# CallerID_V11.net
KiCad netlist of a schematic drawn in EAGLE
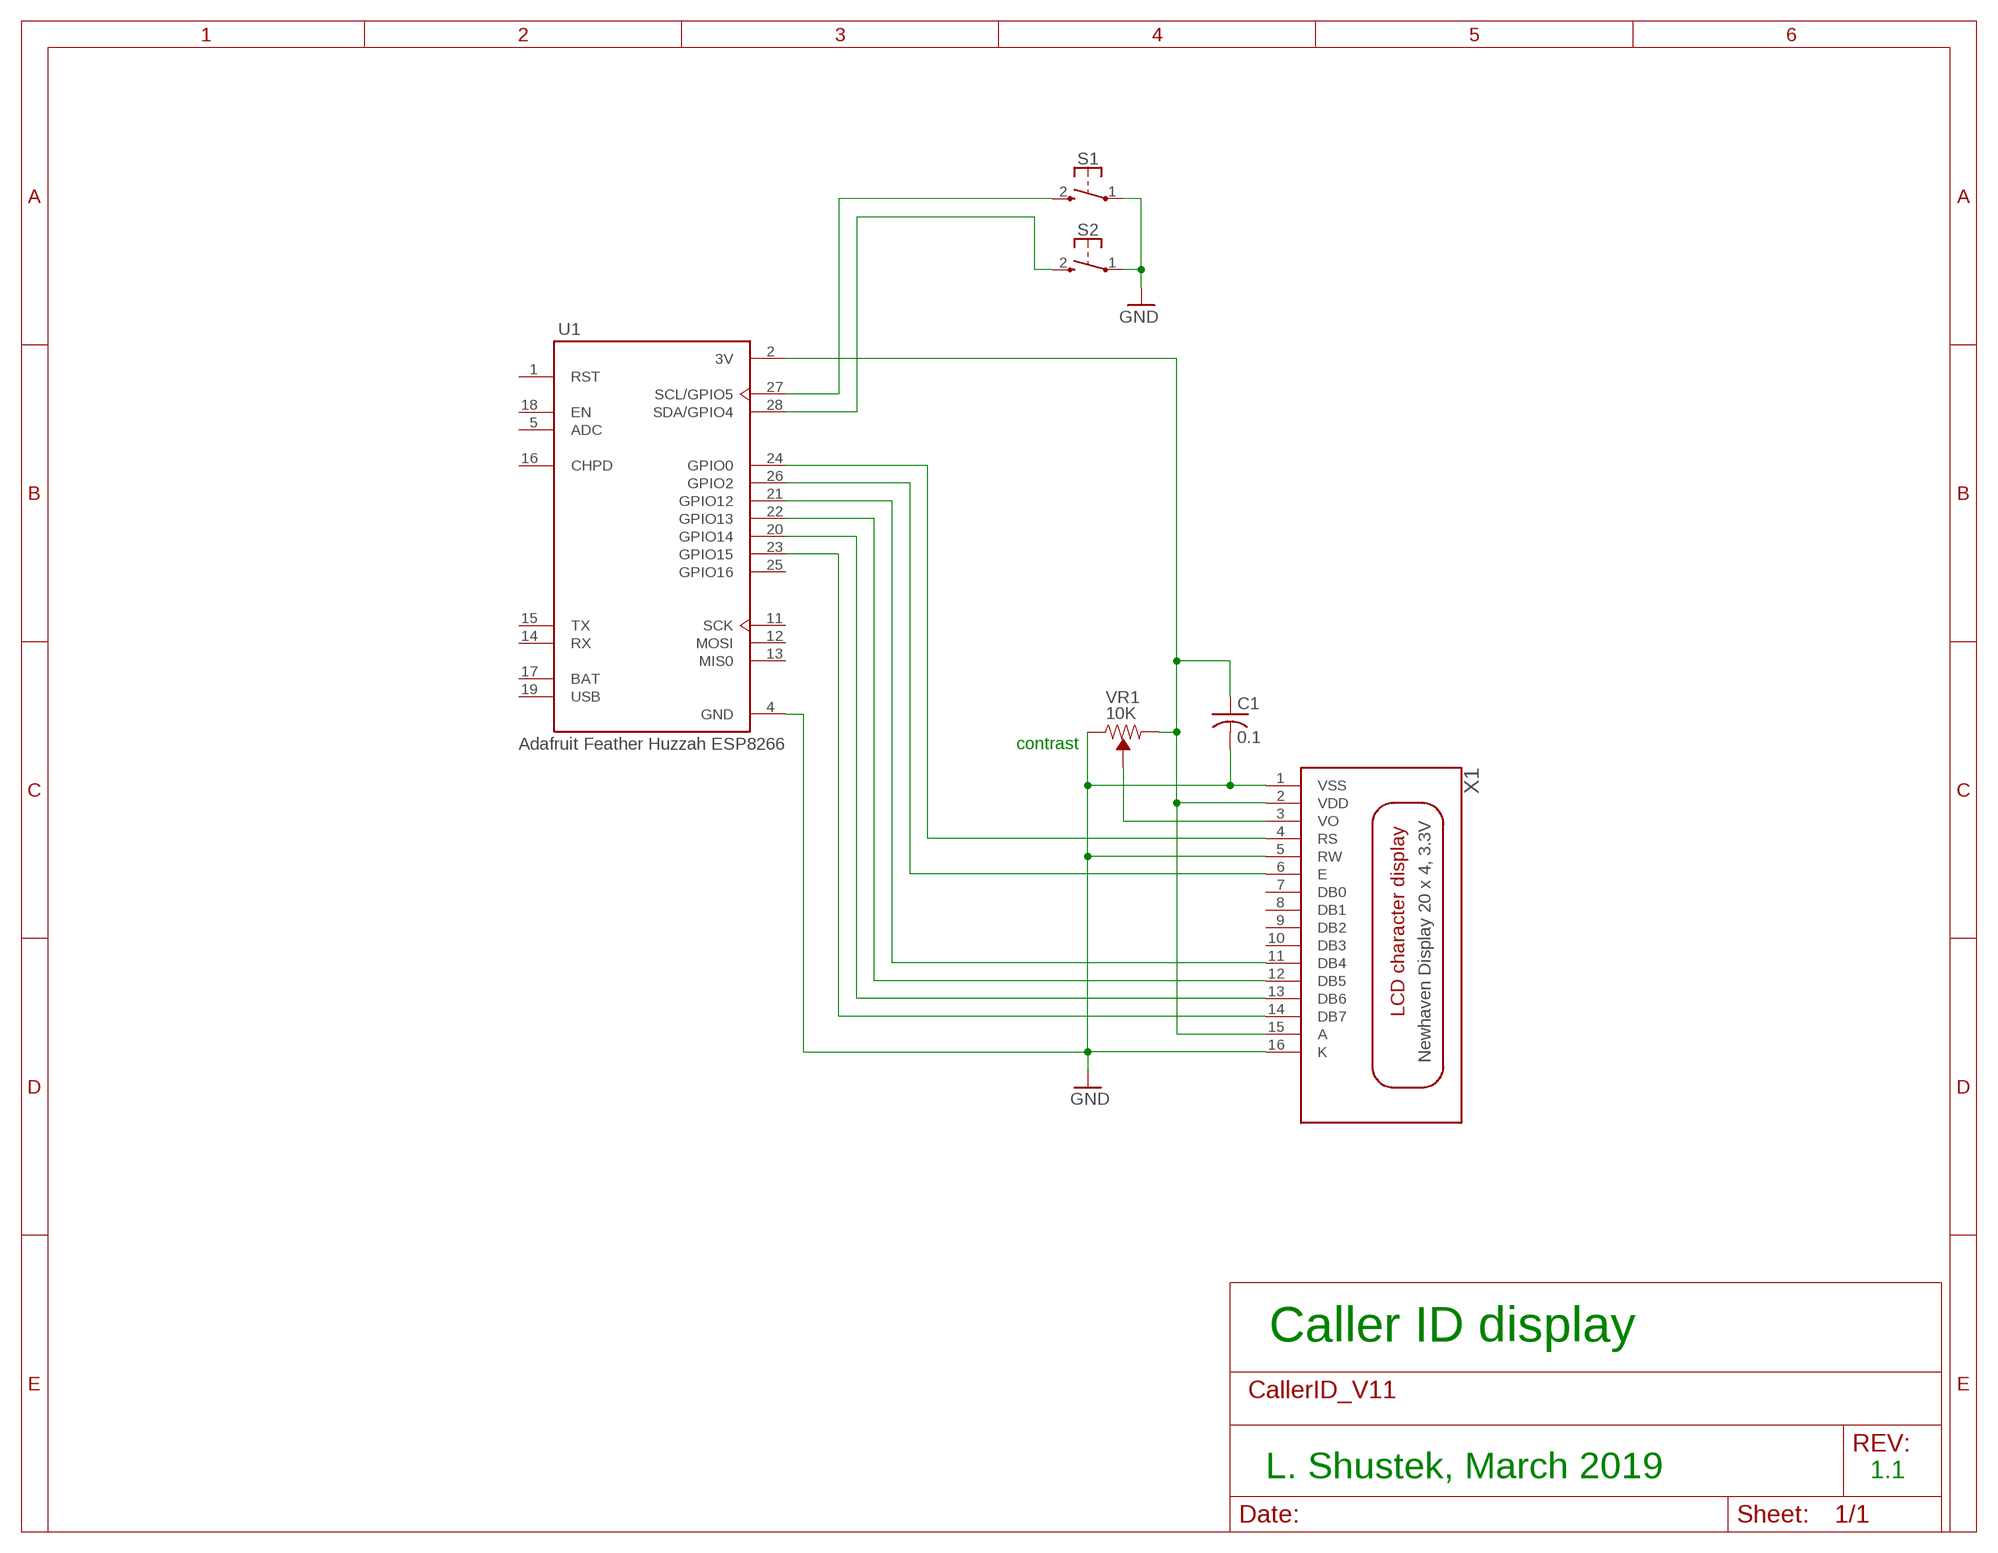
[diagram p0: schematic, sheet 1]

(export (version "E")
  (design (tool "Eeschema 10.0.6"))
  (components
    (comp (ref "C1")
      (value "0.1")
      (footprint "eagle-import:C050-024X044")
      (libsource (lib "eagle-import") (part "C-US050-024X044"))
    )
    (comp (ref "S1")
      (value "PUSHBUTTON-SPST")
      (footprint "eagle-import:PUSHBUTTON-SPST")
      (libsource (lib "eagle-import") (part "PUSHBUTTON-SPST"))
    )
    (comp (ref "S2")
      (value "PUSHBUTTON-SPST")
      (footprint "eagle-import:PUSHBUTTON-SPST")
      (libsource (lib "eagle-import") (part "PUSHBUTTON-SPST"))
    )
    (comp (ref "U1")
      (value "Adafruit Feather Huzzah ESP8266")
      (footprint "eagle-import:ADAFRUIT-FEATHER-WIFI")
      (fields (field (name "MF") "Adafruit Industries") (field (name "MP") "2821"))
      (libsource (lib "eagle-import") (part "ADAFRUIT-FEATHER-WIFI"))
    )
    (comp (ref "VR1")
      (value "10K")
      (footprint "eagle-import:TRIMBOT-BOURNS-3362M")
      (libsource (lib "eagle-import") (part "TRIMPOT"))
    )
    (comp (ref "X1")
      (value "Newhaven Display 20 x 4, 3.3V")
      (footprint "eagle-import:LCD-CHARACTER-DISPLAY-20X4-NEWHAVEN")
      (libsource (lib "eagle-import") (part "LCD-CHARACTER-DISPLAYLCD-CHARACTER-DISPLAY-20X4-NEWHAVEN"))
    )
  )
  (nets
    (net (code "1") (name "GND") (class "Default")
      (node (ref "C1") (pin "2") (pinfunction "2_2") (pintype "passive"))
      (node (ref "S1") (pin "1") (pinfunction "1_1") (pintype "passive"))
      (node (ref "S2") (pin "1") (pinfunction "1_1") (pintype "passive"))
      (node (ref "U1") (pin "4") (pinfunction "GND_4") (pintype "power_in"))
      (node (ref "VR1") (pin "3") (pinfunction "CW_3") (pintype "passive"))
      (node (ref "X1") (pin "1") (pinfunction "VSS_1") (pintype "power_in"))
      (node (ref "X1") (pin "16") (pinfunction "K_16") (pintype "input"))
      (node (ref "X1") (pin "5") (pinfunction "RW_5") (pintype "input"))
    )
    (net (code "2") (name "Net-(S1-3)") (class "Default")
      (node (ref "S1") (pin "2") (pinfunction "3_2") (pintype "passive"))
      (node (ref "U1") (pin "27") (pinfunction "SCL/GPIO5_27") (pintype "bidirectional"))
    )
    (net (code "3") (name "Net-(S2-3)") (class "Default")
      (node (ref "S2") (pin "2") (pinfunction "3_2") (pintype "passive"))
      (node (ref "U1") (pin "28") (pinfunction "SDA/GPIO4_28") (pintype "bidirectional"))
    )
    (net (code "4") (name "Net-(U1-3V)") (class "Default")
      (node (ref "C1") (pin "1") (pinfunction "1_1") (pintype "passive"))
      (node (ref "U1") (pin "2") (pinfunction "3V_2") (pintype "power_in"))
      (node (ref "VR1") (pin "1") (pinfunction "CCW_1") (pintype "passive"))
      (node (ref "X1") (pin "15") (pinfunction "A_15") (pintype "input"))
      (node (ref "X1") (pin "2") (pinfunction "VDD_2") (pintype "power_in"))
    )
    (net (code "5") (name "Net-(U1-GPIO0)") (class "Default")
      (node (ref "U1") (pin "24") (pinfunction "GPIO0_24") (pintype "bidirectional"))
      (node (ref "X1") (pin "4") (pinfunction "RS_4") (pintype "input"))
    )
    (net (code "6") (name "Net-(U1-GPIO2)") (class "Default")
      (node (ref "U1") (pin "26") (pinfunction "GPIO2_26") (pintype "bidirectional"))
      (node (ref "X1") (pin "6") (pinfunction "E_6") (pintype "input"))
    )
    (net (code "7") (name "Net-(U1-GPIO12)") (class "Default")
      (node (ref "U1") (pin "21") (pinfunction "GPIO12_21") (pintype "bidirectional"))
      (node (ref "X1") (pin "11") (pinfunction "DB4_11") (pintype "bidirectional"))
    )
    (net (code "8") (name "Net-(U1-GPIO13)") (class "Default")
      (node (ref "U1") (pin "22") (pinfunction "GPIO13_22") (pintype "bidirectional"))
      (node (ref "X1") (pin "12") (pinfunction "DB5_12") (pintype "bidirectional"))
    )
    (net (code "9") (name "Net-(U1-GPIO14)") (class "Default")
      (node (ref "U1") (pin "20") (pinfunction "GPIO14_20") (pintype "bidirectional"))
      (node (ref "X1") (pin "13") (pinfunction "DB6_13") (pintype "bidirectional"))
    )
    (net (code "10") (name "Net-(U1-GPIO15)") (class "Default")
      (node (ref "U1") (pin "23") (pinfunction "GPIO15_23") (pintype "bidirectional"))
      (node (ref "X1") (pin "14") (pinfunction "DB7_14") (pintype "bidirectional"))
    )
    (net (code "11") (name "Net-(VR1-WIPER)") (class "Default")
      (node (ref "VR1") (pin "2") (pinfunction "WIPER_2") (pintype "passive"))
      (node (ref "X1") (pin "3") (pinfunction "VO_3") (pintype "input"))
    )
    (net (code "12") (name "unconnected-(U1-ADC-Pad5)") (class "Default")
      (node (ref "U1") (pin "5") (pinfunction "ADC_5") (pintype "bidirectional"))
    )
    (net (code "13") (name "unconnected-(U1-BAT-Pad17)") (class "Default")
      (node (ref "U1") (pin "17") (pinfunction "BAT_17") (pintype "bidirectional"))
    )
    (net (code "14") (name "unconnected-(U1-CHPD-Pad16)") (class "Default")
      (node (ref "U1") (pin "16") (pinfunction "CHPD_16") (pintype "bidirectional"))
    )
    (net (code "15") (name "unconnected-(U1-EN-Pad18)") (class "Default")
      (node (ref "U1") (pin "18") (pinfunction "EN_18") (pintype "input"))
    )
    (net (code "16") (name "unconnected-(U1-GPIO16-Pad25)") (class "Default")
      (node (ref "U1") (pin "25") (pinfunction "GPIO16_25") (pintype "bidirectional"))
    )
    (net (code "17") (name "unconnected-(U1-MIS0-Pad13)") (class "Default")
      (node (ref "U1") (pin "13") (pinfunction "MIS0_13") (pintype "input"))
    )
    (net (code "18") (name "unconnected-(U1-MOSI-Pad12)") (class "Default")
      (node (ref "U1") (pin "12") (pinfunction "MOSI_12") (pintype "output"))
    )
    (net (code "19") (name "unconnected-(U1-RST-Pad1)") (class "Default")
      (node (ref "U1") (pin "1") (pinfunction "RST_1") (pintype "input"))
    )
    (net (code "20") (name "unconnected-(U1-RX-Pad14)") (class "Default")
      (node (ref "U1") (pin "14") (pinfunction "RX_14") (pintype "input"))
    )
    (net (code "21") (name "unconnected-(U1-SCK-Pad11)") (class "Default")
      (node (ref "U1") (pin "11") (pinfunction "SCK_11") (pintype "bidirectional"))
    )
    (net (code "22") (name "unconnected-(U1-TX-Pad15)") (class "Default")
      (node (ref "U1") (pin "15") (pinfunction "TX_15") (pintype "output"))
    )
    (net (code "23") (name "unconnected-(U1-USB-Pad19)") (class "Default")
      (node (ref "U1") (pin "19") (pinfunction "USB_19") (pintype "bidirectional"))
    )
    (net (code "24") (name "unconnected-(X1-DB0-Pad7)") (class "Default")
      (node (ref "X1") (pin "7") (pinfunction "DB0_7") (pintype "bidirectional"))
    )
    (net (code "25") (name "unconnected-(X1-DB1-Pad8)") (class "Default")
      (node (ref "X1") (pin "8") (pinfunction "DB1_8") (pintype "bidirectional"))
    )
    (net (code "26") (name "unconnected-(X1-DB2-Pad9)") (class "Default")
      (node (ref "X1") (pin "9") (pinfunction "DB2_9") (pintype "bidirectional"))
    )
    (net (code "27") (name "unconnected-(X1-DB3-Pad10)") (class "Default")
      (node (ref "X1") (pin "10") (pinfunction "DB3_10") (pintype "bidirectional"))
    )
  )
)
